# Communications_Board.net
KiCad netlist of a schematic drawn in EAGLE
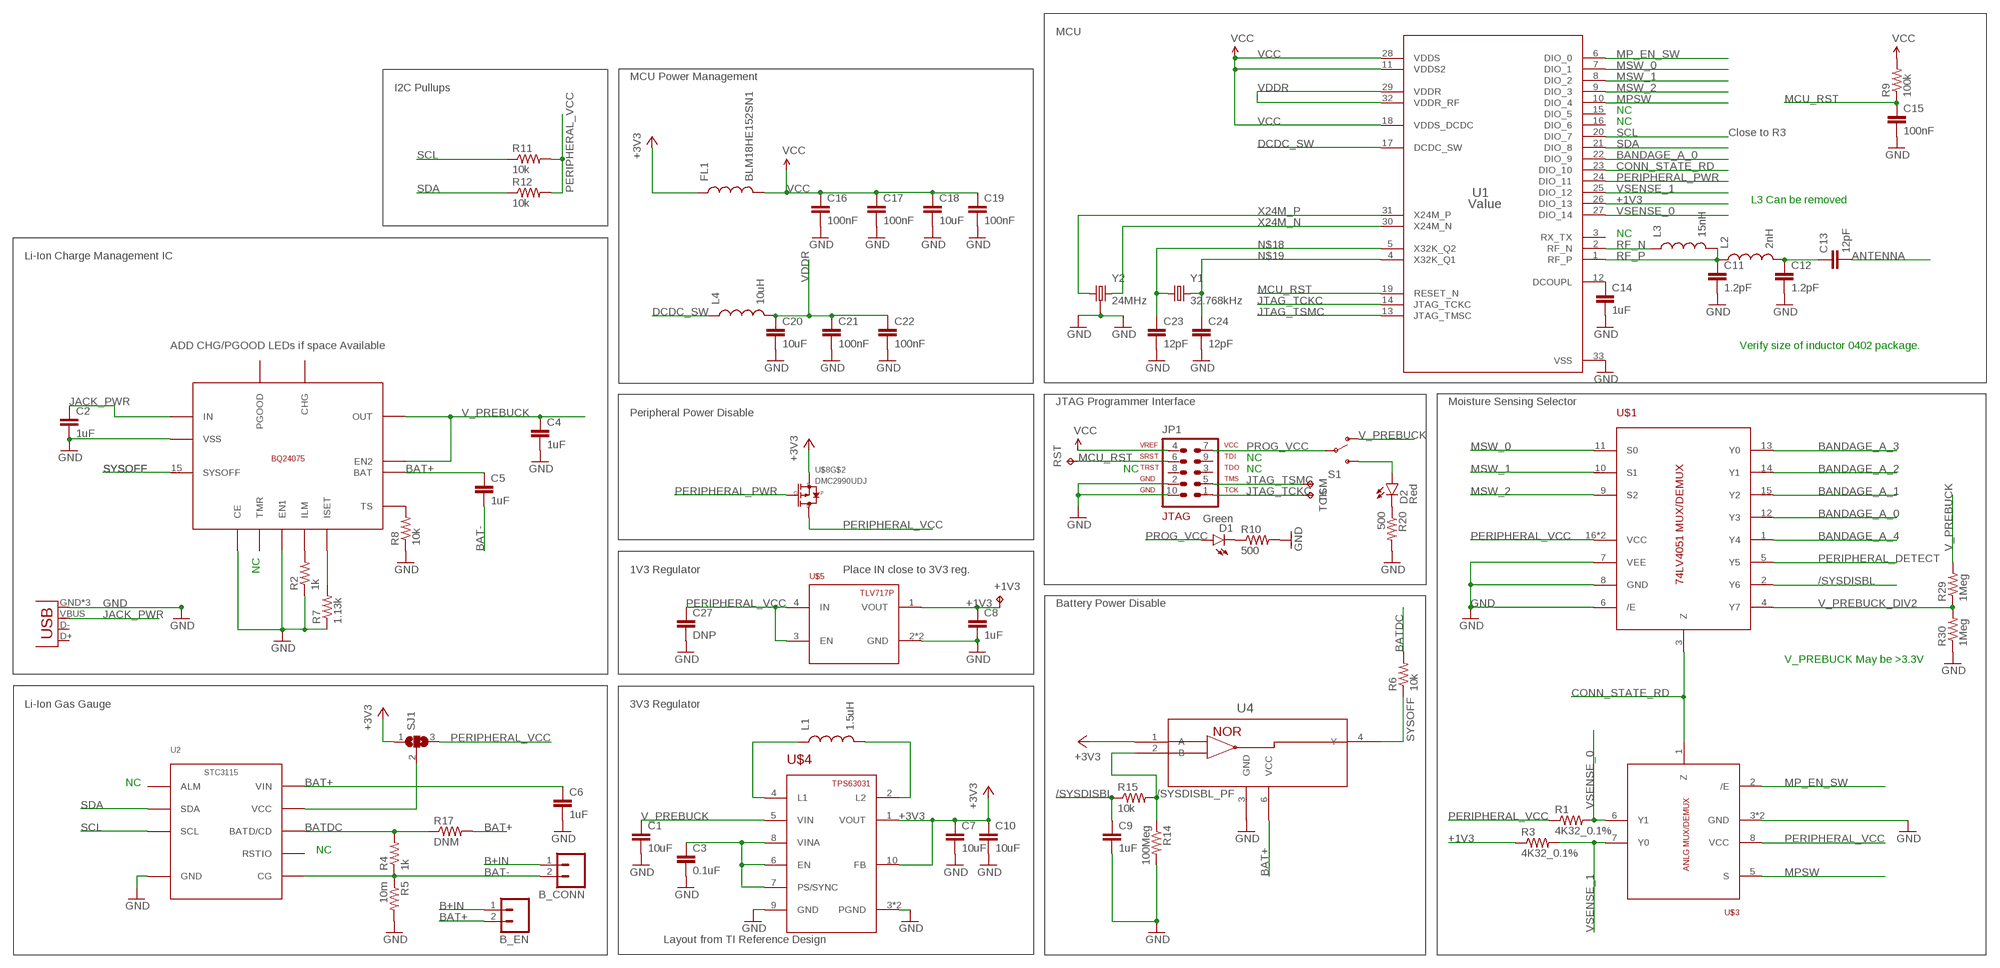
[diagram p0: schematic, sheet 1]
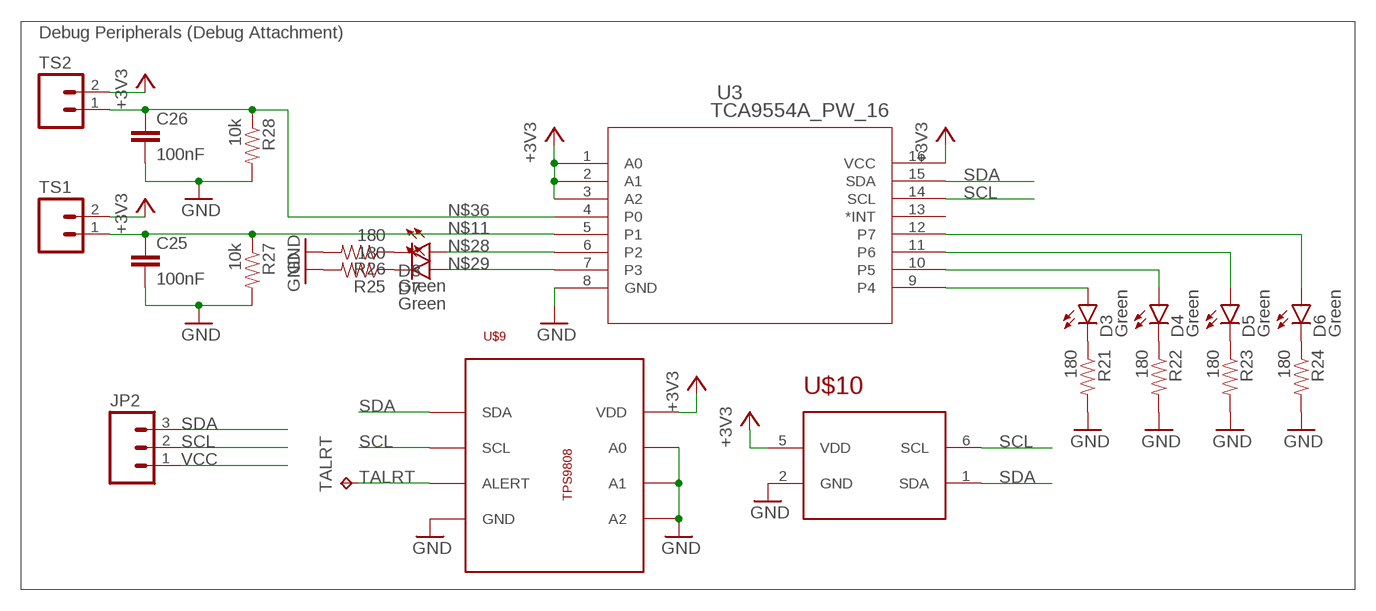
[diagram p1: schematic, sheet 2]
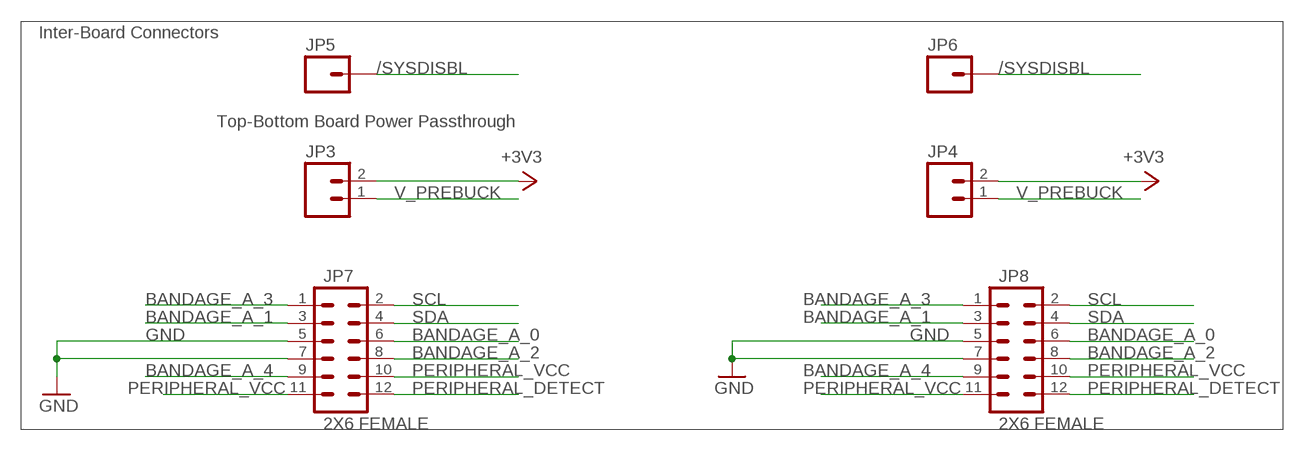
[diagram p2: schematic, sheet 3]

(export (version "E")
  (design (tool "Eeschema 10.0.6"))
  (components
    (comp (ref "JP3")
      (value "M021X02_NO_SILK")
      (footprint "eagle-import:1X02_NO_SILK")
      (libsource (lib "eagle-import") (part "M021X02_NO_SILK"))
    )
    (comp (ref "JP4")
      (value "M021X02_NO_SILK")
      (footprint "eagle-import:1X02_NO_SILK")
      (libsource (lib "eagle-import") (part "M021X02_NO_SILK"))
    )
    (comp (ref "JP5")
      (value "M01PTH")
      (footprint "eagle-import:1X01")
      (libsource (lib "eagle-import") (part "M01PTH"))
    )
    (comp (ref "JP6")
      (value "M01PTH")
      (footprint "eagle-import:1X01")
      (libsource (lib "eagle-import") (part "M01PTH"))
    )
    (comp (ref "JP7")
      (value "2X6 FEMALE")
      (footprint "eagle-import:2X6")
      (libsource (lib "eagle-import") (part "M06X2PTH_FEMALE"))
    )
    (comp (ref "JP8")
      (value "2X6 FEMALE")
      (footprint "eagle-import:2X6")
      (libsource (lib "eagle-import") (part "M06X2PTH_FEMALE"))
    )
    (comp (ref "C25")
      (value "100nF")
      (footprint "eagle-import:0402-CAP")
      (libsource (lib "eagle-import") (part "SparkFun-Passives_CAP0402-CAP"))
    )
    (comp (ref "C26")
      (value "100nF")
      (footprint "eagle-import:0402-CAP")
      (libsource (lib "eagle-import") (part "SparkFun-Passives_CAP0402-CAP"))
    )
    (comp (ref "D3")
      (value "Green")
      (footprint "eagle-import:LED-1206")
      (libsource (lib "eagle-import") (part "LED1206"))
    )
    (comp (ref "D4")
      (value "Green")
      (footprint "eagle-import:LED-1206")
      (libsource (lib "eagle-import") (part "LED1206"))
    )
    (comp (ref "D5")
      (value "Green")
      (footprint "eagle-import:LED-1206")
      (libsource (lib "eagle-import") (part "LED1206"))
    )
    (comp (ref "D6")
      (value "Green")
      (footprint "eagle-import:LED-1206")
      (libsource (lib "eagle-import") (part "LED1206"))
    )
    (comp (ref "D7")
      (value "Green")
      (footprint "eagle-import:LED-1206")
      (libsource (lib "eagle-import") (part "LED1206"))
    )
    (comp (ref "D8")
      (value "Green")
      (footprint "eagle-import:LED-1206")
      (libsource (lib "eagle-import") (part "LED1206"))
    )
    (comp (ref "JP2")
      (value "M03PTH")
      (footprint "eagle-import:1X03")
      (libsource (lib "eagle-import") (part "M03PTH"))
    )
    (comp (ref "R21")
      (value "180")
      (footprint "eagle-import:0603-RES")
      (libsource (lib "eagle-import") (part "RESISTOR0603-RES"))
    )
    (comp (ref "R22")
      (value "180")
      (footprint "eagle-import:0603-RES")
      (libsource (lib "eagle-import") (part "RESISTOR0603-RES"))
    )
    (comp (ref "R23")
      (value "180")
      (footprint "eagle-import:0603-RES")
      (libsource (lib "eagle-import") (part "RESISTOR0603-RES"))
    )
    (comp (ref "R24")
      (value "180")
      (footprint "eagle-import:0603-RES")
      (libsource (lib "eagle-import") (part "RESISTOR0603-RES"))
    )
    (comp (ref "R25")
      (value "180")
      (footprint "eagle-import:0603-RES")
      (libsource (lib "eagle-import") (part "RESISTOR0603-RES"))
    )
    (comp (ref "R26")
      (value "180")
      (footprint "eagle-import:0603-RES")
      (libsource (lib "eagle-import") (part "RESISTOR0603-RES"))
    )
    (comp (ref "R27")
      (value "10k")
      (footprint "eagle-import:0603-RES")
      (libsource (lib "eagle-import") (part "RESISTOR0603-RES"))
    )
    (comp (ref "R28")
      (value "10k")
      (footprint "eagle-import:0603-RES")
      (libsource (lib "eagle-import") (part "RESISTOR0603-RES"))
    )
    (comp (ref "TALRT")
      (value "TPTP17R")
      (footprint "eagle-import:TP17R")
      (libsource (lib "eagle-import") (part "TPTP17R"))
    )
    (comp (ref "TS1")
      (value "M02PTH")
      (footprint "eagle-import:1X02")
      (libsource (lib "eagle-import") (part "M02PTH"))
    )
    (comp (ref "TS2")
      (value "M02PTH")
      (footprint "eagle-import:1X02")
      (libsource (lib "eagle-import") (part "M02PTH"))
    )
    (comp (ref "U$9")
      (value "MCP9808")
      (footprint "eagle-import:MSOP8")
      (libsource (lib "eagle-import") (part "MCP9808"))
    )
    (comp (ref "U$10")
      (value "HDC1050")
      (footprint "eagle-import:SON-6")
      (libsource (lib "eagle-import") (part "HDC1050"))
    )
    (comp (ref "U3")
      (value "TCA9554A_PW_16")
      (footprint "eagle-import:PW16")
      (fields
        (field (name "GENERIC_PART_NUMBER") "TCA9554A")
        (field (name "MANUFACTURER") "Texas Instruments")
        (field (name "MANUFACTURER_PART_NUMBER") "tca9554a_pw_16")
      )
      (libsource (lib "eagle-import") (part "TCA9554A_PW_16"))
    )
    (comp (ref "+1V3")
      (value "TPTP10R")
      (footprint "eagle-import:TP10R")
      (libsource (lib "eagle-import") (part "TPTP10R"))
    )
    (comp (ref "B_CONN")
      (value "M02PTH")
      (footprint "eagle-import:1X02")
      (libsource (lib "eagle-import") (part "M02PTH"))
    )
    (comp (ref "B_EN")
      (value "M02PTH")
      (footprint "eagle-import:1X02")
      (libsource (lib "eagle-import") (part "M02PTH"))
    )
    (comp (ref "C1")
      (value "10uF")
      (footprint "eagle-import:0402-CAP")
      (libsource (lib "eagle-import") (part "SparkFun-Passives_CAP0402-CAP"))
    )
    (comp (ref "C2")
      (value "1uF")
      (footprint "eagle-import:0603-CAP")
      (libsource (lib "eagle-import") (part "CAP0603-CAP"))
    )
    (comp (ref "C3")
      (value "0.1uF")
      (footprint "eagle-import:0402-CAP")
      (libsource (lib "eagle-import") (part "SparkFun-Passives_CAP0402-CAP"))
    )
    (comp (ref "C4")
      (value "1uF")
      (footprint "eagle-import:0603-CAP")
      (libsource (lib "eagle-import") (part "CAP0603-CAP"))
    )
    (comp (ref "C5")
      (value "1uF")
      (footprint "eagle-import:0603-CAP")
      (libsource (lib "eagle-import") (part "CAP0603-CAP"))
    )
    (comp (ref "C6")
      (value "1uF")
      (footprint "eagle-import:0603-CAP")
      (libsource (lib "eagle-import") (part "CAP0603-CAP"))
    )
    (comp (ref "C7")
      (value "10uF")
      (footprint "eagle-import:0402-CAP")
      (libsource (lib "eagle-import") (part "SparkFun-Passives_CAP0402-CAP"))
    )
    (comp (ref "C8")
      (value "1uF")
      (footprint "eagle-import:0402-CAP")
      (libsource (lib "eagle-import") (part "SparkFun-Passives_CAP0402-CAP"))
    )
    (comp (ref "C9")
      (value "1uF")
      (footprint "eagle-import:0603-CAP")
      (libsource (lib "eagle-import") (part "SparkFun-Passives_CAP0603-CAP"))
    )
    (comp (ref "C10")
      (value "10uF")
      (footprint "eagle-import:0603-CAP")
      (libsource (lib "eagle-import") (part "SparkFun-Passives_CAP0603-CAP"))
    )
    (comp (ref "C11")
      (value "1.2pF")
      (footprint "eagle-import:0402-CAP")
      (libsource (lib "eagle-import") (part "SparkFun-Passives_CAP0402-CAP"))
    )
    (comp (ref "C12")
      (value "1.2pF")
      (footprint "eagle-import:0402-CAP")
      (libsource (lib "eagle-import") (part "SparkFun-Passives_CAP0402-CAP"))
    )
    (comp (ref "C13")
      (value "12pF")
      (footprint "eagle-import:0402-CAP")
      (libsource (lib "eagle-import") (part "SparkFun-Passives_CAP0402-CAP"))
    )
    (comp (ref "C14")
      (value "1uF")
      (footprint "eagle-import:0402-CAP")
      (libsource (lib "eagle-import") (part "SparkFun-Passives_CAP0402-CAP"))
    )
    (comp (ref "C15")
      (value "100nF")
      (footprint "eagle-import:0402-CAP")
      (libsource (lib "eagle-import") (part "SparkFun-Passives_CAP0402-CAP"))
    )
    (comp (ref "C16")
      (value "100nF")
      (footprint "eagle-import:0402-CAP")
      (libsource (lib "eagle-import") (part "SparkFun-Passives_CAP0402-CAP"))
    )
    (comp (ref "C17")
      (value "100nF")
      (footprint "eagle-import:0402-CAP")
      (libsource (lib "eagle-import") (part "SparkFun-Passives_CAP0402-CAP"))
    )
    (comp (ref "C18")
      (value "10uF")
      (footprint "eagle-import:0402-CAP")
      (libsource (lib "eagle-import") (part "SparkFun-Passives_CAP0402-CAP"))
    )
    (comp (ref "C19")
      (value "100nF")
      (footprint "eagle-import:0402-CAP")
      (libsource (lib "eagle-import") (part "SparkFun-Passives_CAP0402-CAP"))
    )
    (comp (ref "C20")
      (value "10uF")
      (footprint "eagle-import:0402-CAP")
      (libsource (lib "eagle-import") (part "SparkFun-Passives_CAP0402-CAP"))
    )
    (comp (ref "C21")
      (value "100nF")
      (footprint "eagle-import:0402-CAP")
      (libsource (lib "eagle-import") (part "SparkFun-Passives_CAP0402-CAP"))
    )
    (comp (ref "C22")
      (value "100nF")
      (footprint "eagle-import:0402-CAP")
      (libsource (lib "eagle-import") (part "SparkFun-Passives_CAP0402-CAP"))
    )
    (comp (ref "C23")
      (value "12pF")
      (footprint "eagle-import:0402-CAP")
      (libsource (lib "eagle-import") (part "SparkFun-Passives_CAP0402-CAP"))
    )
    (comp (ref "C24")
      (value "12pF")
      (footprint "eagle-import:0402-CAP")
      (libsource (lib "eagle-import") (part "SparkFun-Passives_CAP0402-CAP"))
    )
    (comp (ref "C27")
      (value "DNP")
      (footprint "eagle-import:0402-CAP")
      (libsource (lib "eagle-import") (part "SparkFun-Passives_CAP0402-CAP"))
    )
    (comp (ref "D1")
      (value "Green")
      (footprint "eagle-import:LED-1206")
      (libsource (lib "eagle-import") (part "LED1206"))
    )
    (comp (ref "D2")
      (value "Red")
      (footprint "eagle-import:LED-1206")
      (libsource (lib "eagle-import") (part "LED1206"))
    )
    (comp (ref "FL1")
      (value "BLM18HE152SN1")
      (footprint "eagle-import:0603")
      (libsource (lib "eagle-import") (part "INDUCTOR0603"))
    )
    (comp (ref "JP1")
      (value "AVR-JTAG-10")
      (footprint "eagle-import:AVR-JTAG-10")
      (libsource (lib "eagle-import") (part "AVR-JTAG-10"))
    )
    (comp (ref "L1")
      (value "1.5uH")
      (footprint "eagle-import:IND1212")
      (libsource (lib "eagle-import") (part "INDUCTOR"))
    )
    (comp (ref "L2")
      (value "2nH")
      (footprint "eagle-import:C0402")
      (libsource (lib "eagle-import") (part "SparkFun-Passives_INDUCTOR0402"))
    )
    (comp (ref "L3")
      (value "15nH")
      (footprint "eagle-import:C0402")
      (libsource (lib "eagle-import") (part "SparkFun-Passives_INDUCTOR0402"))
    )
    (comp (ref "L4")
      (value "10uH")
      (footprint "eagle-import:0603")
      (libsource (lib "eagle-import") (part "INDUCTOR0603"))
    )
    (comp (ref "R1")
      (value "4K32_0.1%")
      (footprint "eagle-import:0402-RES")
      (libsource (lib "eagle-import") (part "RESISTOR0402-RES"))
    )
    (comp (ref "R2")
      (value "1k")
      (footprint "eagle-import:0603-RES")
      (libsource (lib "eagle-import") (part "RESISTOR0603-RES"))
    )
    (comp (ref "R3")
      (value "4K32_0.1%")
      (footprint "eagle-import:0402-RES")
      (libsource (lib "eagle-import") (part "RESISTOR0402-RES"))
    )
    (comp (ref "R4")
      (value "1k")
      (footprint "eagle-import:0603-RES")
      (libsource (lib "eagle-import") (part "RESISTOR0603-RES"))
    )
    (comp (ref "R5")
      (value "10m")
      (footprint "eagle-import:0603-RES")
      (libsource (lib "eagle-import") (part "RESISTOR0603-RES"))
    )
    (comp (ref "R6")
      (value "10k")
      (footprint "eagle-import:0603-RES")
      (libsource (lib "eagle-import") (part "RESISTOR0603-RES"))
    )
    (comp (ref "R7")
      (value "1.13k")
      (footprint "eagle-import:0603-RES")
      (libsource (lib "eagle-import") (part "RESISTOR0603-RES"))
    )
    (comp (ref "R8")
      (value "10k")
      (footprint "eagle-import:0603-RES")
      (libsource (lib "eagle-import") (part "RESISTOR0603-RES"))
    )
    (comp (ref "R9")
      (value "100k")
      (footprint "eagle-import:0603-RES")
      (libsource (lib "eagle-import") (part "RESISTOR0603-RES"))
    )
    (comp (ref "R10")
      (value "500")
      (footprint "eagle-import:0603-RES")
      (libsource (lib "eagle-import") (part "RESISTOR0603-RES"))
    )
    (comp (ref "R11")
      (value "10k")
      (footprint "eagle-import:0603-RES")
      (libsource (lib "eagle-import") (part "RESISTOR0603-RES"))
    )
    (comp (ref "R12")
      (value "10k")
      (footprint "eagle-import:0603-RES")
      (libsource (lib "eagle-import") (part "RESISTOR0603-RES"))
    )
    (comp (ref "R14")
      (value "100Meg")
      (footprint "eagle-import:0603-RES")
      (libsource (lib "eagle-import") (part "RESISTOR0603-RES"))
    )
    (comp (ref "R15")
      (value "10k")
      (footprint "eagle-import:0603-RES")
      (libsource (lib "eagle-import") (part "RESISTOR0603-RES"))
    )
    (comp (ref "R17")
      (value "DNM")
      (footprint "eagle-import:0603-RES")
      (libsource (lib "eagle-import") (part "RESISTOR0603-RES"))
    )
    (comp (ref "R20")
      (value "500")
      (footprint "eagle-import:0603-RES")
      (libsource (lib "eagle-import") (part "RESISTOR0603-RES"))
    )
    (comp (ref "R29")
      (value "1Meg")
      (footprint "eagle-import:0402-RES")
      (libsource (lib "eagle-import") (part "RESISTOR0402-RES"))
    )
    (comp (ref "R30")
      (value "1Meg")
      (footprint "eagle-import:0402-RES")
      (libsource (lib "eagle-import") (part "RESISTOR0402-RES"))
    )
    (comp (ref "RST")
      (value "TPTP10R")
      (footprint "eagle-import:TP10R")
      (libsource (lib "eagle-import") (part "TPTP10R"))
    )
    (comp (ref "S1")
      (value "SWITCH-SPDT")
      (footprint "eagle-import:JS102011SAQN")
      (libsource (lib "eagle-import") (part "SWITCH-SPDT"))
    )
    (comp (ref "SJ1")
      (value "SJ2W")
      (footprint "eagle-import:SJ_2")
      (libsource (lib "eagle-import") (part "SJ2W"))
    )
    (comp (ref "TCK")
      (value "TPTP10R")
      (footprint "eagle-import:TP10R")
      (libsource (lib "eagle-import") (part "TPTP10R"))
    )
    (comp (ref "TSM")
      (value "TPTP10R")
      (footprint "eagle-import:TP10R")
      (libsource (lib "eagle-import") (part "TPTP10R"))
    )
    (comp (ref "U$1")
      (value "74LV4051")
      (footprint "eagle-import:SOT763-1")
      (libsource (lib "eagle-import") (part "74LV4051"))
    )
    (comp (ref "U$2")
      (value "BQ24075")
      (footprint "eagle-import:QFN16-3X3MM")
      (libsource (lib "eagle-import") (part "BQ24075"))
    )
    (comp (ref "U$3")
      (value "74LVC2G53")
      (footprint "eagle-import:SOT833-1")
      (libsource (lib "eagle-import") (part "74LVC2G53"))
    )
    (comp (ref "U$4")
      (value "TPS63031")
      (footprint "eagle-import:SON-10")
      (libsource (lib "eagle-import") (part "TPS63031"))
    )
    (comp (ref "U$5")
      (value "TLV717P")
      (footprint "eagle-import:X2SON")
      (libsource (lib "eagle-import") (part "TLV717P"))
    )
    (comp (ref "U$8")
      (value "DMC2990UDJ")
      (footprint "eagle-import:SOT963")
      (libsource (lib "eagle-import") (part "DMC2990UDJ"))
    )
    (comp (ref "U1")
      (value "Value")
      (footprint "eagle-import:RHB0032E")
      (fields
        (field (name "ALTERNATEPARTNUMBER") "CC2640F128RHBT")
        (field (name "MANUFACTURER") "Texas Instruments")
        (field (name "PARTNUMBER") "CC2640F128RHBR")
      )
      (libsource (lib "eagle-import") (part "CC2640F128RHBR"))
    )
    (comp (ref "U2")
      (value "STC3115")
      (footprint "eagle-import:DFN10-2X3")
      (libsource (lib "eagle-import") (part "STC3115"))
    )
    (comp (ref "U4")
      (value "SN74AUP1G02_DSF_6")
      (footprint "eagle-import:DSF6")
      (fields
        (field (name "GENERIC_PART_NUMBER") "SN74AUP1G02")
        (field (name "MANUFACTURER") "Texas Instruments")
        (field (name "MANUFACTURER_PART_NUMBER") "sn74aup1g02_dsf_6")
      )
      (libsource (lib "eagle-import") (part "SN74AUP1G02_DSF_6"))
    )
    (comp (ref "X2")
      (value "USB-MICROB")
      (footprint "eagle-import:USB-MICROB")
      (libsource (lib "eagle-import") (part "USB-MICROB"))
    )
    (comp (ref "Y1")
      (value "32.768kHz")
      (footprint "eagle-import:CRYSTAL-3.2X1.5")
      (libsource (lib "eagle-import") (part "CRYSTAL"))
    )
    (comp (ref "Y2")
      (value "24MHz")
      (footprint "eagle-import:TSX-3225")
      (libsource (lib "eagle-import") (part "CRYSTAL-GROUNDED"))
    )
  )
  (nets
    (net (code "1") (name "+1V3") (class "Default")
      (node (ref "+1V3") (pin "TP") (pinfunction "TP_TP") (pintype "input"))
      (node (ref "C8") (pin "1") (pinfunction "1_1") (pintype "passive"))
      (node (ref "R3") (pin "1") (pinfunction "1_1") (pintype "passive"))
      (node (ref "U$5") (pin "1") (pinfunction "VOUT_1") (pintype "bidirectional"))
      (node (ref "U1") (pin "26") (pinfunction "DIO_13_26") (pintype "bidirectional"))
    )
    (net (code "2") (name "+3V3") (class "Default")
      (node (ref "C10") (pin "1") (pinfunction "1_1") (pintype "passive"))
      (node (ref "C7") (pin "1") (pinfunction "1_1") (pintype "passive"))
      (node (ref "FL1") (pin "1") (pinfunction "1_1") (pintype "passive"))
      (node (ref "JP3") (pin "2") (pinfunction "2_2") (pintype "passive"))
      (node (ref "JP4") (pin "2") (pinfunction "2_2") (pintype "passive"))
      (node (ref "SJ1") (pin "1") (pinfunction "1_1") (pintype "passive"))
      (node (ref "TS1") (pin "2") (pinfunction "2_2") (pintype "passive"))
      (node (ref "TS2") (pin "2") (pinfunction "2_2") (pintype "passive"))
      (node (ref "U$10") (pin "5") (pinfunction "VDD_5") (pintype "bidirectional"))
      (node (ref "U$4") (pin "1") (pinfunction "VOUT_1") (pintype "bidirectional"))
      (node (ref "U$4") (pin "10") (pinfunction "FB_10") (pintype "bidirectional"))
      (node (ref "U$8") (pin "4") (pinfunction "S_4") (pintype "passive"))
      (node (ref "U$9") (pin "8") (pinfunction "VDD_8") (pintype "bidirectional"))
      (node (ref "U3") (pin "1") (pinfunction "A0_1") (pintype "input"))
      (node (ref "U3") (pin "16") (pinfunction "VCC_16") (pintype "power_in"))
      (node (ref "U3") (pin "2") (pinfunction "A1_2") (pintype "input"))
      (node (ref "U3") (pin "3") (pinfunction "A2_3") (pintype "input"))
      (node (ref "U4") (pin "1") (pinfunction "A_1") (pintype "input"))
    )
    (net (code "3") (name "ANTENNA") (class "Default")
      (node (ref "C13") (pin "2") (pinfunction "2_2") (pintype "passive"))
    )
    (net (code "4") (name "B+IN") (class "Default")
      (node (ref "B_CONN") (pin "1") (pinfunction "1_1") (pintype "passive"))
      (node (ref "B_EN") (pin "1") (pinfunction "1_1") (pintype "passive"))
    )
    (net (code "5") (name "BANDAGE_A_0") (class "Default")
      (node (ref "JP7") (pin "6") (pinfunction "6_6") (pintype "passive"))
      (node (ref "JP8") (pin "6") (pinfunction "6_6") (pintype "passive"))
      (node (ref "U$1") (pin "12") (pinfunction "Y3_12") (pintype "bidirectional"))
      (node (ref "U1") (pin "22") (pinfunction "DIO_9_22") (pintype "bidirectional"))
    )
    (net (code "6") (name "BANDAGE_A_1") (class "Default")
      (node (ref "JP7") (pin "3") (pinfunction "3_3") (pintype "passive"))
      (node (ref "JP8") (pin "3") (pinfunction "3_3") (pintype "passive"))
      (node (ref "U$1") (pin "15") (pinfunction "Y2_15") (pintype "bidirectional"))
    )
    (net (code "7") (name "BANDAGE_A_2") (class "Default")
      (node (ref "JP7") (pin "8") (pinfunction "8_8") (pintype "passive"))
      (node (ref "JP8") (pin "8") (pinfunction "8_8") (pintype "passive"))
      (node (ref "U$1") (pin "14") (pinfunction "Y1_14") (pintype "bidirectional"))
    )
    (net (code "8") (name "BANDAGE_A_3") (class "Default")
      (node (ref "JP7") (pin "1") (pinfunction "1_1") (pintype "passive"))
      (node (ref "JP8") (pin "1") (pinfunction "1_1") (pintype "passive"))
      (node (ref "U$1") (pin "13") (pinfunction "Y0_13") (pintype "bidirectional"))
    )
    (net (code "9") (name "BANDAGE_A_4") (class "Default")
      (node (ref "JP7") (pin "9") (pinfunction "9_9") (pintype "passive"))
      (node (ref "JP8") (pin "9") (pinfunction "9_9") (pintype "passive"))
      (node (ref "U$1") (pin "1") (pinfunction "Y4_1") (pintype "bidirectional"))
    )
    (net (code "10") (name "BAT+") (class "Default")
      (node (ref "B_EN") (pin "2") (pinfunction "2_2") (pintype "passive"))
      (node (ref "C5") (pin "1") (pinfunction "1_1") (pintype "passive"))
      (node (ref "C6") (pin "1") (pinfunction "1_1") (pintype "passive"))
      (node (ref "R17") (pin "2") (pinfunction "2_2") (pintype "passive"))
      (node (ref "U$2") (pin "2") (pinfunction "BAT_2") (pintype "bidirectional"))
      (node (ref "U$2") (pin "3") (pinfunction "BAT_3") (pintype "bidirectional"))
      (node (ref "U2") (pin "P10") (pinfunction "VIN_P10") (pintype "bidirectional"))
      (node (ref "U4") (pin "6") (pinfunction "VCC_6") (pintype "power_in"))
    )
    (net (code "11") (name "BAT-") (class "Default")
      (node (ref "B_CONN") (pin "2") (pinfunction "2_2") (pintype "passive"))
      (node (ref "C5") (pin "2") (pinfunction "2_2") (pintype "passive"))
      (node (ref "R4") (pin "1") (pinfunction "1_1") (pintype "passive"))
      (node (ref "R5") (pin "1") (pinfunction "1_1") (pintype "passive"))
      (node (ref "U2") (pin "P6") (pinfunction "CG_P6") (pintype "bidirectional"))
    )
    (net (code "12") (name "BATDC") (class "Default")
      (node (ref "R17") (pin "1") (pinfunction "1_1") (pintype "passive"))
      (node (ref "R4") (pin "2") (pinfunction "2_2") (pintype "passive"))
      (node (ref "R6") (pin "2") (pinfunction "2_2") (pintype "passive"))
      (node (ref "U2") (pin "P8") (pinfunction "BATD/CD_P8") (pintype "bidirectional"))
    )
    (net (code "13") (name "CONN_STATE_RD") (class "Default")
      (node (ref "U$1") (pin "3") (pinfunction "Z_3") (pintype "bidirectional"))
      (node (ref "U$3") (pin "1") (pinfunction "Z_1") (pintype "bidirectional"))
      (node (ref "U1") (pin "23") (pinfunction "DIO_10_23") (pintype "bidirectional"))
    )
    (net (code "14") (name "DCDC_SW") (class "Default")
      (node (ref "L4") (pin "1") (pinfunction "1_1") (pintype "passive"))
      (node (ref "U1") (pin "17") (pinfunction "DCDC_SW_17") (pintype "power_in"))
    )
    (net (code "15") (name "GND") (class "Default")
      (node (ref "C1") (pin "2") (pinfunction "2_2") (pintype "passive"))
      (node (ref "C10") (pin "2") (pinfunction "2_2") (pintype "passive"))
      (node (ref "C11") (pin "2") (pinfunction "2_2") (pintype "passive"))
      (node (ref "C12") (pin "2") (pinfunction "2_2") (pintype "passive"))
      (node (ref "C14") (pin "2") (pinfunction "2_2") (pintype "passive"))
      (node (ref "C15") (pin "2") (pinfunction "2_2") (pintype "passive"))
      (node (ref "C16") (pin "2") (pinfunction "2_2") (pintype "passive"))
      (node (ref "C17") (pin "2") (pinfunction "2_2") (pintype "passive"))
      (node (ref "C18") (pin "2") (pinfunction "2_2") (pintype "passive"))
      (node (ref "C19") (pin "2") (pinfunction "2_2") (pintype "passive"))
      (node (ref "C2") (pin "2") (pinfunction "2_2") (pintype "passive"))
      (node (ref "C20") (pin "2") (pinfunction "2_2") (pintype "passive"))
      (node (ref "C21") (pin "2") (pinfunction "2_2") (pintype "passive"))
      (node (ref "C22") (pin "2") (pinfunction "2_2") (pintype "passive"))
      (node (ref "C23") (pin "2") (pinfunction "2_2") (pintype "passive"))
      (node (ref "C24") (pin "2") (pinfunction "2_2") (pintype "passive"))
      (node (ref "C25") (pin "2") (pinfunction "2_2") (pintype "passive"))
      (node (ref "C26") (pin "2") (pinfunction "2_2") (pintype "passive"))
      (node (ref "C27") (pin "2") (pinfunction "2_2") (pintype "passive"))
      (node (ref "C3") (pin "2") (pinfunction "2_2") (pintype "passive"))
      (node (ref "C4") (pin "2") (pinfunction "2_2") (pintype "passive"))
      (node (ref "C6") (pin "2") (pinfunction "2_2") (pintype "passive"))
      (node (ref "C7") (pin "2") (pinfunction "2_2") (pintype "passive"))
      (node (ref "C8") (pin "2") (pinfunction "2_2") (pintype "passive"))
      (node (ref "C9") (pin "2") (pinfunction "2_2") (pintype "passive"))
      (node (ref "JP1") (pin "10") (pinfunction "10_10") (pintype "passive"))
      (node (ref "JP1") (pin "2") (pinfunction "2_2") (pintype "passive"))
      (node (ref "JP7") (pin "5") (pinfunction "5_5") (pintype "passive"))
      (node (ref "JP7") (pin "7") (pinfunction "7_7") (pintype "passive"))
      (node (ref "JP8") (pin "5") (pinfunction "5_5") (pintype "passive"))
      (node (ref "JP8") (pin "7") (pinfunction "7_7") (pintype "passive"))
      (node (ref "R10") (pin "2") (pinfunction "2_2") (pintype "passive"))
      (node (ref "R14") (pin "2") (pinfunction "2_2") (pintype "passive"))
      (node (ref "R2") (pin "1") (pinfunction "1_1") (pintype "passive"))
      (node (ref "R20") (pin "2") (pinfunction "2_2") (pintype "passive"))
      (node (ref "R21") (pin "2") (pinfunction "2_2") (pintype "passive"))
      (node (ref "R22") (pin "2") (pinfunction "2_2") (pintype "passive"))
      (node (ref "R23") (pin "2") (pinfunction "2_2") (pintype "passive"))
      (node (ref "R24") (pin "2") (pinfunction "2_2") (pintype "passive"))
      (node (ref "R25") (pin "2") (pinfunction "2_2") (pintype "passive"))
      (node (ref "R26") (pin "2") (pinfunction "2_2") (pintype "passive"))
      (node (ref "R27") (pin "2") (pinfunction "2_2") (pintype "passive"))
      (node (ref "R28") (pin "2") (pinfunction "2_2") (pintype "passive"))
      (node (ref "R30") (pin "1") (pinfunction "1_1") (pintype "passive"))
      (node (ref "R5") (pin "2") (pinfunction "2_2") (pintype "passive"))
      (node (ref "R7") (pin "1") (pinfunction "1_1") (pintype "passive"))
      (node (ref "R8") (pin "1") (pinfunction "1_1") (pintype "passive"))
      (node (ref "U$1") (pin "6") (pinfunction "/E_6") (pintype "bidirectional"))
      (node (ref "U$1") (pin "7") (pinfunction "VEE_7") (pintype "bidirectional"))
      (node (ref "U$1") (pin "8") (pinfunction "GND_8") (pintype "bidirectional"))
      (node (ref "U$10") (pin "2") (pinfunction "GND_2") (pintype "bidirectional"))
      (node (ref "U$2") (pin "4") (pinfunction "CE_4") (pintype "bidirectional"))
      (node (ref "U$2") (pin "6") (pinfunction "EN1_6") (pintype "bidirectional"))
      (node (ref "U$2") (pin "8") (pinfunction "VSS_8") (pintype "bidirectional"))
      (node (ref "U$2") (pin "EXT") (pinfunction "VSS_EXT") (pintype "bidirectional"))
      (node (ref "U$3") (pin "3") (pinfunction "GND_3") (pintype "bidirectional"))
      (node (ref "U$3") (pin "4") (pinfunction "GND_4") (pintype "bidirectional"))
      (node (ref "U$4") (pin "3") (pinfunction "PGND_3") (pintype "bidirectional"))
      (node (ref "U$4") (pin "9") (pinfunction "GND_9") (pintype "bidirectional"))
      (node (ref "U$4") (pin "PAD") (pinfunction "PGND_PAD") (pintype "bidirectional"))
      (node (ref "U$5") (pin "2") (pinfunction "GND_2") (pintype "bidirectional"))
      (node (ref "U$5") (pin "PAD") (pinfunction "GND_PAD") (pintype "bidirectional"))
      (node (ref "U$9") (pin "4") (pinfunction "GND_4") (pintype "bidirectional"))
      (node (ref "U$9") (pin "5") (pinfunction "A2_5") (pintype "bidirectional"))
      (node (ref "U$9") (pin "6") (pinfunction "A1_6") (pintype "bidirectional"))
      (node (ref "U$9") (pin "7") (pinfunction "A0_7") (pintype "bidirectional"))
      (node (ref "U1") (pin "33") (pinfunction "VSS_33") (pintype "power_in"))
      (node (ref "U2") (pin "P5") (pinfunction "GND_P5") (pintype "bidirectional"))
      (node (ref "U3") (pin "8") (pinfunction "GND_8") (pintype "power_in"))
      (node (ref "U4") (pin "3") (pinfunction "GND_3") (pintype "power_in"))
      (node (ref "X2") (pin "GND") (pinfunction "GND_GND") (pintype "bidirectional"))
      (node (ref "X2") (pin "MT1") (pinfunction "GND_MT1") (pintype "bidirectional"))
      (node (ref "X2") (pin "MT2") (pinfunction "GND_MT2") (pintype "bidirectional"))
      (node (ref "Y2") (pin "2") (pinfunction "3_2") (pintype "passive"))
      (node (ref "Y2") (pin "4") (pinfunction "3_4") (pintype "passive"))
    )
    (net (code "16") (name "JACK_PWR") (class "Default")
      (node (ref "C2") (pin "1") (pinfunction "1_1") (pintype "passive"))
      (node (ref "U$2") (pin "13") (pinfunction "IN_13") (pintype "bidirectional"))
      (node (ref "X2") (pin "VBUS") (pinfunction "VBUS_VBUS") (pintype "bidirectional"))
    )
    (net (code "17") (name "JTAG_TCKC") (class "Default")
      (node (ref "JP1") (pin "1") (pinfunction "1_1") (pintype "passive"))
      (node (ref "TCK") (pin "TP") (pinfunction "TP_TP") (pintype "input"))
      (node (ref "U1") (pin "14") (pinfunction "JTAG_TCKC_14") (pintype "bidirectional"))
    )
    (net (code "18") (name "JTAG_TSMC") (class "Default")
      (node (ref "JP1") (pin "5") (pinfunction "5_5") (pintype "passive"))
      (node (ref "TSM") (pin "TP") (pinfunction "TP_TP") (pintype "input"))
      (node (ref "U1") (pin "13") (pinfunction "JTAG_TMSC_13") (pintype "bidirectional"))
    )
    (net (code "19") (name "MCU_RST") (class "Default")
      (node (ref "C15") (pin "1") (pinfunction "1_1") (pintype "passive"))
      (node (ref "JP1") (pin "6") (pinfunction "6_6") (pintype "passive"))
      (node (ref "R9") (pin "1") (pinfunction "1_1") (pintype "passive"))
      (node (ref "RST") (pin "TP") (pinfunction "TP_TP") (pintype "input"))
      (node (ref "U1") (pin "19") (pinfunction "RESET_N_19") (pintype "input"))
    )
    (net (code "20") (name "MPSW") (class "Default")
      (node (ref "U$3") (pin "5") (pinfunction "S_5") (pintype "bidirectional"))
      (node (ref "U1") (pin "10") (pinfunction "DIO_4_10") (pintype "bidirectional"))
    )
    (net (code "21") (name "MP_EN_SW") (class "Default")
      (node (ref "U$3") (pin "2") (pinfunction "/E_2") (pintype "bidirectional"))
      (node (ref "U1") (pin "6") (pinfunction "DIO_0_6") (pintype "bidirectional"))
    )
    (net (code "22") (name "MSW_0") (class "Default")
      (node (ref "U$1") (pin "11") (pinfunction "S0_11") (pintype "bidirectional"))
      (node (ref "U1") (pin "7") (pinfunction "DIO_1_7") (pintype "bidirectional"))
    )
    (net (code "23") (name "MSW_1") (class "Default")
      (node (ref "U$1") (pin "10") (pinfunction "S1_10") (pintype "bidirectional"))
      (node (ref "U1") (pin "8") (pinfunction "DIO_2_8") (pintype "bidirectional"))
    )
    (net (code "24") (name "MSW_2") (class "Default")
      (node (ref "U$1") (pin "9") (pinfunction "S2_9") (pintype "bidirectional"))
      (node (ref "U1") (pin "9") (pinfunction "DIO_3_9") (pintype "bidirectional"))
    )
    (net (code "25") (name "N$11") (class "Default")
      (node (ref "C25") (pin "1") (pinfunction "1_1") (pintype "passive"))
      (node (ref "R27") (pin "1") (pinfunction "1_1") (pintype "passive"))
      (node (ref "TS1") (pin "1") (pinfunction "1_1") (pintype "passive"))
      (node (ref "U3") (pin "5") (pinfunction "P1_5") (pintype "bidirectional"))
    )
    (net (code "26") (name "N$18") (class "Default")
      (node (ref "C23") (pin "1") (pinfunction "1_1") (pintype "passive"))
      (node (ref "U1") (pin "5") (pinfunction "X32K_Q2_5") (pintype "bidirectional"))
      (node (ref "Y1") (pin "1") (pinfunction "1_1") (pintype "passive"))
    )
    (net (code "27") (name "N$19") (class "Default")
      (node (ref "C24") (pin "1") (pinfunction "1_1") (pintype "passive"))
      (node (ref "U1") (pin "4") (pinfunction "X32K_Q1_4") (pintype "bidirectional"))
      (node (ref "Y1") (pin "2") (pinfunction "2_2") (pintype "passive"))
    )
    (net (code "28") (name "N$28") (class "Default")
      (node (ref "D8") (pin "A") (pinfunction "A_A") (pintype "passive"))
      (node (ref "U3") (pin "6") (pinfunction "P2_6") (pintype "bidirectional"))
    )
    (net (code "29") (name "N$29") (class "Default")
      (node (ref "D7") (pin "A") (pinfunction "A_A") (pintype "passive"))
      (node (ref "U3") (pin "7") (pinfunction "P3_7") (pintype "bidirectional"))
    )
    (net (code "30") (name "N$36") (class "Default")
      (node (ref "C26") (pin "1") (pinfunction "1_1") (pintype "passive"))
      (node (ref "R28") (pin "1") (pinfunction "1_1") (pintype "passive"))
      (node (ref "TS2") (pin "1") (pinfunction "1_1") (pintype "passive"))
      (node (ref "U3") (pin "4") (pinfunction "P0_4") (pintype "bidirectional"))
    )
    (net (code "31") (name "Net-(C12-Pad1)") (class "Default")
      (node (ref "C12") (pin "1") (pinfunction "1_1") (pintype "passive"))
      (node (ref "C13") (pin "1") (pinfunction "1_1") (pintype "passive"))
      (node (ref "L2") (pin "2") (pinfunction "2_2") (pintype "passive"))
    )
    (net (code "32") (name "Net-(D1-PadC)") (class "Default")
      (node (ref "D1") (pin "C") (pinfunction "C_C") (pintype "passive"))
      (node (ref "R10") (pin "1") (pinfunction "1_1") (pintype "passive"))
    )
    (net (code "33") (name "Net-(D2-PadC)") (class "Default")
      (node (ref "D2") (pin "C") (pinfunction "C_C") (pintype "passive"))
      (node (ref "R20") (pin "1") (pinfunction "1_1") (pintype "passive"))
    )
    (net (code "34") (name "Net-(D3-PadC)") (class "Default")
      (node (ref "D3") (pin "C") (pinfunction "C_C") (pintype "passive"))
      (node (ref "R21") (pin "1") (pinfunction "1_1") (pintype "passive"))
    )
    (net (code "35") (name "Net-(D4-PadC)") (class "Default")
      (node (ref "D4") (pin "C") (pinfunction "C_C") (pintype "passive"))
      (node (ref "R22") (pin "1") (pinfunction "1_1") (pintype "passive"))
    )
    (net (code "36") (name "Net-(D5-PadC)") (class "Default")
      (node (ref "D5") (pin "C") (pinfunction "C_C") (pintype "passive"))
      (node (ref "R23") (pin "1") (pinfunction "1_1") (pintype "passive"))
    )
    (net (code "37") (name "Net-(D6-PadC)") (class "Default")
      (node (ref "D6") (pin "C") (pinfunction "C_C") (pintype "passive"))
      (node (ref "R24") (pin "1") (pinfunction "1_1") (pintype "passive"))
    )
    (net (code "38") (name "Net-(D7-PadC)") (class "Default")
      (node (ref "D7") (pin "C") (pinfunction "C_C") (pintype "passive"))
      (node (ref "R25") (pin "1") (pinfunction "1_1") (pintype "passive"))
    )
    (net (code "39") (name "Net-(D8-PadC)") (class "Default")
      (node (ref "D8") (pin "C") (pinfunction "C_C") (pintype "passive"))
      (node (ref "R26") (pin "1") (pinfunction "1_1") (pintype "passive"))
    )
    (net (code "40") (name "Net-(L1-1)") (class "Default")
      (node (ref "L1") (pin "P$1") (pinfunction "1_P$1") (pintype "passive"))
      (node (ref "U$4") (pin "4") (pinfunction "L1_4") (pintype "bidirectional"))
    )
    (net (code "41") (name "Net-(L1-2)") (class "Default")
      (node (ref "L1") (pin "P$2") (pinfunction "2_P$2") (pintype "passive"))
      (node (ref "U$4") (pin "2") (pinfunction "L2_2") (pintype "bidirectional"))
    )
    (net (code "42") (name "Net-(S1-S)") (class "Default")
      (node (ref "D2") (pin "A") (pinfunction "A_A") (pintype "passive"))
      (node (ref "S1") (pin "3") (pinfunction "S_3") (pintype "passive"))
    )
    (net (code "43") (name "Net-(U$2-ILM)") (class "Default")
      (node (ref "R2") (pin "2") (pinfunction "2_2") (pintype "passive"))
      (node (ref "U$2") (pin "12") (pinfunction "ILM_12") (pintype "bidirectional"))
    )
    (net (code "44") (name "Net-(U$2-ISET)") (class "Default")
      (node (ref "R7") (pin "2") (pinfunction "2_2") (pintype "passive"))
      (node (ref "U$2") (pin "16") (pinfunction "ISET_16") (pintype "bidirectional"))
    )
    (net (code "45") (name "Net-(U$2-TS)") (class "Default")
      (node (ref "R8") (pin "2") (pinfunction "2_2") (pintype "passive"))
      (node (ref "U$2") (pin "1") (pinfunction "TS_1") (pintype "bidirectional"))
    )
    (net (code "46") (name "Net-(U$4-EN)") (class "Default")
      (node (ref "C3") (pin "1") (pinfunction "1_1") (pintype "passive"))
      (node (ref "U$4") (pin "6") (pinfunction "EN_6") (pintype "bidirectional"))
      (node (ref "U$4") (pin "7") (pinfunction "PS/SYNC_7") (pintype "bidirectional"))
      (node (ref "U$4") (pin "8") (pinfunction "VINA_8") (pintype "bidirectional"))
    )
    (net (code "47") (name "Net-(U1-DCOUPL)") (class "Default")
      (node (ref "C14") (pin "1") (pinfunction "1_1") (pintype "passive"))
      (node (ref "U1") (pin "12") (pinfunction "DCOUPL_12") (pintype "power_in"))
    )
    (net (code "48") (name "Net-(U2-VCC)") (class "Default")
      (node (ref "SJ1") (pin "2") (pinfunction "2_2") (pintype "passive"))
      (node (ref "U2") (pin "P9") (pinfunction "VCC_P9") (pintype "bidirectional"))
    )
    (net (code "49") (name "Net-(U3-P4)") (class "Default")
      (node (ref "D3") (pin "A") (pinfunction "A_A") (pintype "passive"))
      (node (ref "U3") (pin "9") (pinfunction "P4_9") (pintype "bidirectional"))
    )
    (net (code "50") (name "Net-(U3-P5)") (class "Default")
      (node (ref "D4") (pin "A") (pinfunction "A_A") (pintype "passive"))
      (node (ref "U3") (pin "10") (pinfunction "P5_10") (pintype "bidirectional"))
    )
    (net (code "51") (name "Net-(U3-P6)") (class "Default")
      (node (ref "D5") (pin "A") (pinfunction "A_A") (pintype "passive"))
      (node (ref "U3") (pin "11") (pinfunction "P6_11") (pintype "bidirectional"))
    )
    (net (code "52") (name "Net-(U3-P7)") (class "Default")
      (node (ref "D6") (pin "A") (pinfunction "A_A") (pintype "passive"))
      (node (ref "U3") (pin "12") (pinfunction "P7_12") (pintype "bidirectional"))
    )
    (net (code "53") (name "PERIPHERAL_DETECT") (class "Default")
      (node (ref "JP7") (pin "12") (pinfunction "12_12") (pintype "passive"))
      (node (ref "JP8") (pin "12") (pinfunction "12_12") (pintype "passive"))
      (node (ref "U$1") (pin "5") (pinfunction "Y5_5") (pintype "bidirectional"))
    )
    (net (code "54") (name "PERIPHERAL_PWR") (class "Default")
      (node (ref "U$8") (pin "5") (pinfunction "G_5") (pintype "passive"))
      (node (ref "U1") (pin "24") (pinfunction "DIO_11_24") (pintype "bidirectional"))
    )
    (net (code "55") (name "PERIPHERAL_VCC") (class "Default")
      (node (ref "C27") (pin "1") (pinfunction "1_1") (pintype "passive"))
      (node (ref "JP7") (pin "10") (pinfunction "10_10") (pintype "passive"))
      (node (ref "JP7") (pin "11") (pinfunction "11_11") (pintype "passive"))
      (node (ref "JP8") (pin "10") (pinfunction "10_10") (pintype "passive"))
      (node (ref "JP8") (pin "11") (pinfunction "11_11") (pintype "passive"))
      (node (ref "R1") (pin "1") (pinfunction "1_1") (pintype "passive"))
      (node (ref "R11") (pin "2") (pinfunction "2_2") (pintype "passive"))
      (node (ref "R12") (pin "2") (pinfunction "2_2") (pintype "passive"))
      (node (ref "SJ1") (pin "3") (pinfunction "3_3") (pintype "passive"))
      (node (ref "U$1") (pin "16") (pinfunction "VCC_16") (pintype "bidirectional"))
      (node (ref "U$1") (pin "PAD") (pinfunction "VCC_PAD") (pintype "bidirectional"))
      (node (ref "U$3") (pin "8") (pinfunction "VCC_8") (pintype "bidirectional"))
      (node (ref "U$5") (pin "3") (pinfunction "EN_3") (pintype "bidirectional"))
      (node (ref "U$5") (pin "4") (pinfunction "IN_4") (pintype "bidirectional"))
      (node (ref "U$8") (pin "3") (pinfunction "D_3") (pintype "passive"))
    )
    (net (code "56") (name "PROG_VCC") (class "Default")
      (node (ref "D1") (pin "A") (pinfunction "A_A") (pintype "passive"))
      (node (ref "JP1") (pin "7") (pinfunction "7_7") (pintype "passive"))
      (node (ref "S1") (pin "2") (pinfunction "P_2") (pintype "passive"))
    )
    (net (code "57") (name "RF_N") (class "Default")
      (node (ref "L3") (pin "1") (pinfunction "1_1") (pintype "passive"))
      (node (ref "U1") (pin "2") (pinfunction "RF_N_2") (pintype "bidirectional"))
    )
    (net (code "58") (name "RF_P") (class "Default")
      (node (ref "C11") (pin "1") (pinfunction "1_1") (pintype "passive"))
      (node (ref "L2") (pin "1") (pinfunction "1_1") (pintype "passive"))
      (node (ref "L3") (pin "2") (pinfunction "2_2") (pintype "passive"))
      (node (ref "U1") (pin "1") (pinfunction "RF_P_1") (pintype "bidirectional"))
    )
    (net (code "59") (name "SCL") (class "Default")
      (node (ref "JP2") (pin "2") (pinfunction "2_2") (pintype "passive"))
      (node (ref "JP7") (pin "2") (pinfunction "2_2") (pintype "passive"))
      (node (ref "JP8") (pin "2") (pinfunction "2_2") (pintype "passive"))
      (node (ref "R11") (pin "1") (pinfunction "1_1") (pintype "passive"))
      (node (ref "U$10") (pin "6") (pinfunction "SCL_6") (pintype "bidirectional"))
      (node (ref "U$9") (pin "2") (pinfunction "SCL_2") (pintype "bidirectional"))
      (node (ref "U1") (pin "20") (pinfunction "DIO_7_20") (pintype "bidirectional"))
      (node (ref "U2") (pin "P3") (pinfunction "SCL_P3") (pintype "bidirectional"))
      (node (ref "U3") (pin "14") (pinfunction "SCL_14") (pintype "bidirectional"))
    )
    (net (code "60") (name "SDA") (class "Default")
      (node (ref "JP2") (pin "3") (pinfunction "3_3") (pintype "passive"))
      (node (ref "JP7") (pin "4") (pinfunction "4_4") (pintype "passive"))
      (node (ref "JP8") (pin "4") (pinfunction "4_4") (pintype "passive"))
      (node (ref "R12") (pin "1") (pinfunction "1_1") (pintype "passive"))
      (node (ref "U$10") (pin "1") (pinfunction "SDA_1") (pintype "bidirectional"))
      (node (ref "U$9") (pin "1") (pinfunction "SDA_1") (pintype "bidirectional"))
      (node (ref "U1") (pin "21") (pinfunction "DIO_8_21") (pintype "bidirectional"))
      (node (ref "U2") (pin "P2") (pinfunction "SDA_P2") (pintype "bidirectional"))
      (node (ref "U3") (pin "15") (pinfunction "SDA_15") (pintype "bidirectional"))
    )
    (net (code "61") (name "SYSOFF") (class "Default")
      (node (ref "R6") (pin "1") (pinfunction "1_1") (pintype "passive"))
      (node (ref "U$2") (pin "15") (pinfunction "SYSOFF_15") (pintype "bidirectional"))
      (node (ref "U4") (pin "4") (pinfunction "Y_4") (pintype "output"))
    )
    (net (code "62") (name "TALRT") (class "Default")
      (node (ref "TALRT") (pin "TP") (pinfunction "TP_TP") (pintype "input"))
      (node (ref "U$9") (pin "3") (pinfunction "ALERT_3") (pintype "bidirectional"))
    )
    (net (code "63") (name "VCC") (class "Default")
      (node (ref "C16") (pin "1") (pinfunction "1_1") (pintype "passive"))
      (node (ref "C17") (pin "1") (pinfunction "1_1") (pintype "passive"))
      (node (ref "C18") (pin "1") (pinfunction "1_1") (pintype "passive"))
      (node (ref "C19") (pin "1") (pinfunction "1_1") (pintype "passive"))
      (node (ref "FL1") (pin "2") (pinfunction "2_2") (pintype "passive"))
      (node (ref "JP1") (pin "4") (pinfunction "4_4") (pintype "passive"))
      (node (ref "JP2") (pin "1") (pinfunction "1_1") (pintype "passive"))
      (node (ref "R9") (pin "2") (pinfunction "2_2") (pintype "passive"))
      (node (ref "U1") (pin "11") (pinfunction "VDDS2_11") (pintype "power_in"))
      (node (ref "U1") (pin "18") (pinfunction "VDDS_DCDC_18") (pintype "power_in"))
      (node (ref "U1") (pin "28") (pinfunction "VDDS_28") (pintype "power_in"))
    )
    (net (code "64") (name "VDDR") (class "Default")
      (node (ref "C20") (pin "1") (pinfunction "1_1") (pintype "passive"))
      (node (ref "C21") (pin "1") (pinfunction "1_1") (pintype "passive"))
      (node (ref "C22") (pin "1") (pinfunction "1_1") (pintype "passive"))
      (node (ref "L4") (pin "2") (pinfunction "2_2") (pintype "passive"))
      (node (ref "U1") (pin "29") (pinfunction "VDDR_29") (pintype "power_in"))
      (node (ref "U1") (pin "32") (pinfunction "VDDR_RF_32") (pintype "power_in"))
    )
    (net (code "65") (name "VSENSE_0") (class "Default")
      (node (ref "R1") (pin "2") (pinfunction "2_2") (pintype "passive"))
      (node (ref "U$3") (pin "6") (pinfunction "Y1_6") (pintype "bidirectional"))
      (node (ref "U1") (pin "27") (pinfunction "DIO_14_27") (pintype "bidirectional"))
    )
    (net (code "66") (name "VSENSE_1") (class "Default")
      (node (ref "R3") (pin "2") (pinfunction "2_2") (pintype "passive"))
      (node (ref "U$3") (pin "7") (pinfunction "Y0_7") (pintype "bidirectional"))
      (node (ref "U1") (pin "25") (pinfunction "DIO_12_25") (pintype "bidirectional"))
    )
    (net (code "67") (name "V_PREBUCK") (class "Default")
      (node (ref "C1") (pin "1") (pinfunction "1_1") (pintype "passive"))
      (node (ref "C4") (pin "1") (pinfunction "1_1") (pintype "passive"))
      (node (ref "JP3") (pin "1") (pinfunction "1_1") (pintype "passive"))
      (node (ref "JP4") (pin "1") (pinfunction "1_1") (pintype "passive"))
      (node (ref "R29") (pin "2") (pinfunction "2_2") (pintype "passive"))
      (node (ref "S1") (pin "1") (pinfunction "O_1") (pintype "passive"))
      (node (ref "U$2") (pin "10") (pinfunction "OUT_10") (pintype "power_in"))
      (node (ref "U$2") (pin "11") (pinfunction "OUT_11") (pintype "power_in"))
      (node (ref "U$2") (pin "5") (pinfunction "EN2_5") (pintype "bidirectional"))
      (node (ref "U$4") (pin "5") (pinfunction "VIN_5") (pintype "bidirectional"))
    )
    (net (code "68") (name "V_PREBUCK_DIV2") (class "Default")
      (node (ref "R29") (pin "1") (pinfunction "1_1") (pintype "passive"))
      (node (ref "R30") (pin "2") (pinfunction "2_2") (pintype "passive"))
      (node (ref "U$1") (pin "4") (pinfunction "Y7_4") (pintype "bidirectional"))
    )
    (net (code "69") (name "X24M_N") (class "Default")
      (node (ref "U1") (pin "30") (pinfunction "X24M_N_30") (pintype "bidirectional"))
      (node (ref "Y2") (pin "3") (pinfunction "2_3") (pintype "passive"))
    )
    (net (code "70") (name "X24M_P") (class "Default")
      (node (ref "U1") (pin "31") (pinfunction "X24M_P_31") (pintype "bidirectional"))
      (node (ref "Y2") (pin "1") (pinfunction "1_1") (pintype "passive"))
    )
    (net (code "71") (name "unconnected-(JP1-Pad3)") (class "Default")
      (node (ref "JP1") (pin "3") (pinfunction "3_3") (pintype "passive"))
    )
    (net (code "72") (name "unconnected-(JP1-Pad8)") (class "Default")
      (node (ref "JP1") (pin "8") (pinfunction "8_8") (pintype "passive"))
    )
    (net (code "73") (name "unconnected-(JP1-Pad9)") (class "Default")
      (node (ref "JP1") (pin "9") (pinfunction "9_9") (pintype "passive"))
    )
    (net (code "74") (name "unconnected-(U$2-CHG-Pad9)") (class "Default")
      (node (ref "U$2") (pin "9") (pinfunction "CHG_9") (pintype "bidirectional"))
    )
    (net (code "75") (name "unconnected-(U$2-PGOOD-Pad7)") (class "Default")
      (node (ref "U$2") (pin "7") (pinfunction "PGOOD_7") (pintype "bidirectional"))
    )
    (net (code "76") (name "unconnected-(U$2-TMR-Pad14)") (class "Default")
      (node (ref "U$2") (pin "14") (pinfunction "TMR_14") (pintype "bidirectional"))
    )
    (net (code "77") (name "unconnected-(U1-DIO_5-Pad15)") (class "Default")
      (node (ref "U1") (pin "15") (pinfunction "DIO_5_15") (pintype "bidirectional"))
    )
    (net (code "78") (name "unconnected-(U1-DIO_6-Pad16)") (class "Default")
      (node (ref "U1") (pin "16") (pinfunction "DIO_6_16") (pintype "bidirectional"))
    )
    (net (code "79") (name "unconnected-(U1-RX_TX-Pad3)") (class "Default")
      (node (ref "U1") (pin "3") (pinfunction "RX_TX_3") (pintype "bidirectional"))
    )
    (net (code "80") (name "unconnected-(U2-ALM-PadP1)") (class "Default")
      (node (ref "U2") (pin "P1") (pinfunction "ALM_P1") (pintype "bidirectional"))
    )
    (net (code "81") (name "unconnected-(U2-RSTIO-PadP7)") (class "Default")
      (node (ref "U2") (pin "P7") (pinfunction "RSTIO_P7") (pintype "bidirectional"))
    )
    (net (code "82") (name "unconnected-(U3-*INT-Pad13)") (class "Default")
      (node (ref "U3") (pin "13") (pinfunction "*INT_13") (pintype "output"))
    )
    (net (code "83") (name "unconnected-(X2-PadD+)") (class "Default")
      (node (ref "X2") (pin "D+") (pinfunction "D+_D+") (pintype "bidirectional"))
    )
    (net (code "84") (name "unconnected-(X2-PadD-)") (class "Default")
      (node (ref "X2") (pin "D-") (pinfunction "D-_D-") (pintype "bidirectional"))
    )
    (net (code "85") (name "{slash}SYSDISBL") (class "Default")
      (node (ref "C9") (pin "1") (pinfunction "1_1") (pintype "passive"))
      (node (ref "JP5") (pin "1") (pinfunction "1_1") (pintype "passive"))
      (node (ref "JP6") (pin "1") (pinfunction "1_1") (pintype "passive"))
      (node (ref "R15") (pin "1") (pinfunction "1_1") (pintype "passive"))
      (node (ref "U$1") (pin "2") (pinfunction "Y6_2") (pintype "bidirectional"))
    )
    (net (code "86") (name "{slash}SYSDISBL_PF") (class "Default")
      (node (ref "R14") (pin "1") (pinfunction "1_1") (pintype "passive"))
      (node (ref "R15") (pin "2") (pinfunction "2_2") (pintype "passive"))
      (node (ref "U4") (pin "2") (pinfunction "B_2") (pintype "input"))
    )
  )
)
